# ExtraCore_RST.net
KiCad netlist of a schematic drawn in EAGLE
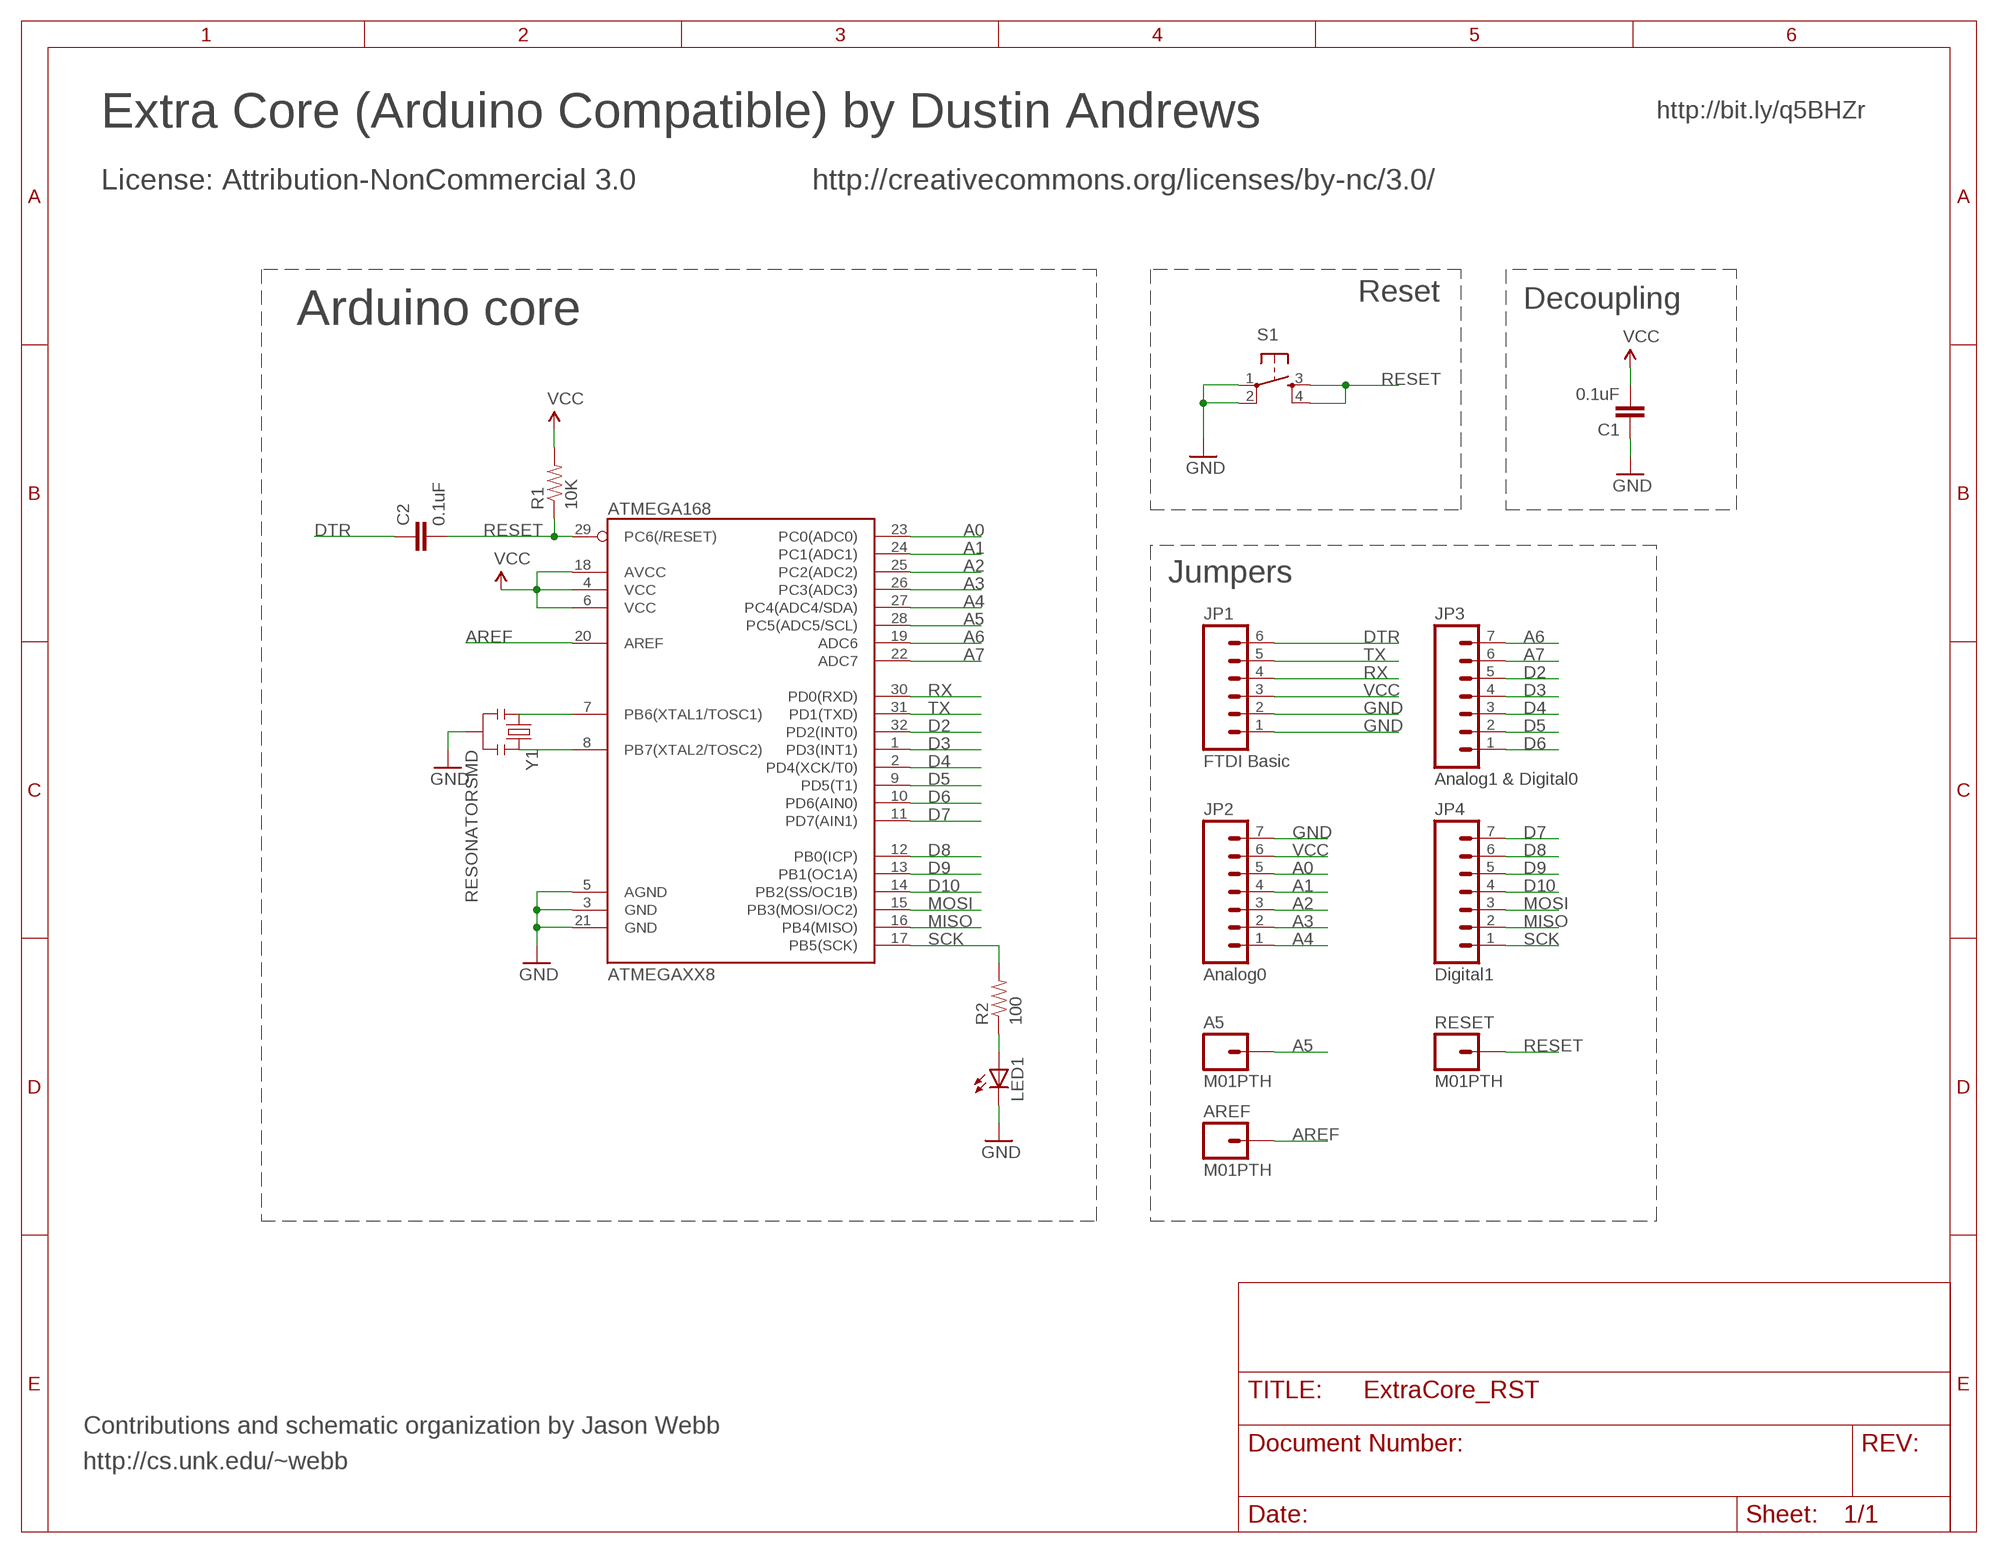
[diagram p0: schematic, sheet 1]

(export (version "E")
  (design (tool "Eeschema 10.0.6"))
  (components
    (comp (ref "A5")
      (value "M01PTH")
      (footprint "eagle-import:1X01")
      (libsource (lib "eagle-import") (part "M01PTH"))
    )
    (comp (ref "AREF")
      (value "M01PTH")
      (footprint "eagle-import:1X01")
      (libsource (lib "eagle-import") (part "M01PTH"))
    )
    (comp (ref "ATMEGAXX8")
      (value "ATMEGA168")
      (footprint "eagle-import:TQFP32-08")
      (libsource (lib "eagle-import") (part "ATMEGA168"))
    )
    (comp (ref "C1")
      (value "0.1uF")
      (footprint "eagle-import:0805")
      (libsource (lib "eagle-import") (part "CAP0805"))
    )
    (comp (ref "C2")
      (value "0.1uF")
      (footprint "eagle-import:0805")
      (libsource (lib "eagle-import") (part "CAP0805"))
    )
    (comp (ref "JP1")
      (value "FTDI Basic")
      (footprint "eagle-import:1X06")
      (libsource (lib "eagle-import") (part "M06SIP"))
    )
    (comp (ref "JP2")
      (value "Analog0")
      (footprint "eagle-import:1X07")
      (libsource (lib "eagle-import") (part "M07"))
    )
    (comp (ref "JP3")
      (value "Analog1 & Digital0")
      (footprint "eagle-import:1X07")
      (libsource (lib "eagle-import") (part "M07"))
    )
    (comp (ref "JP4")
      (value "Digital1")
      (footprint "eagle-import:1X07")
      (libsource (lib "eagle-import") (part "M07"))
    )
    (comp (ref "LED1")
      (value "LEDCHIP-LED0805")
      (footprint "eagle-import:CHIP-LED0805")
      (libsource (lib "eagle-import") (part "LEDCHIP-LED0805"))
    )
    (comp (ref "R1")
      (value "10K")
      (footprint "eagle-import:0805")
      (libsource (lib "eagle-import") (part "RESISTOR0805-RES"))
    )
    (comp (ref "R2")
      (value "100")
      (footprint "eagle-import:0805")
      (libsource (lib "eagle-import") (part "RESISTOR0805-RES"))
    )
    (comp (ref "RESET")
      (value "M01PTH")
      (footprint "eagle-import:1X01")
      (libsource (lib "eagle-import") (part "M01PTH"))
    )
    (comp (ref "S1")
      (value "TAC_SWITCHSMD")
      (footprint "eagle-import:TACTILE_SWITCH_SMD")
      (libsource (lib "eagle-import") (part "TAC_SWITCHSMD"))
    )
    (comp (ref "Y1")
      (value "RESONATORSMD")
      (footprint "eagle-import:RESONATOR-SMD")
      (libsource (lib "eagle-import") (part "RESONATORSMD"))
    )
  )
  (nets
    (net (code "1") (name "/A0") (class "Default")
      (node (ref "ATMEGAXX8") (pin "23") (pinfunction "PC0(ADC0)_23") (pintype "bidirectional"))
      (node (ref "JP2") (pin "5") (pinfunction "5_5") (pintype "passive"))
    )
    (net (code "2") (name "/A1") (class "Default")
      (node (ref "ATMEGAXX8") (pin "24") (pinfunction "PC1(ADC1)_24") (pintype "bidirectional"))
      (node (ref "JP2") (pin "4") (pinfunction "4_4") (pintype "passive"))
    )
    (net (code "3") (name "/A2") (class "Default")
      (node (ref "ATMEGAXX8") (pin "25") (pinfunction "PC2(ADC2)_25") (pintype "bidirectional"))
      (node (ref "JP2") (pin "3") (pinfunction "3_3") (pintype "passive"))
    )
    (net (code "4") (name "/A3") (class "Default")
      (node (ref "ATMEGAXX8") (pin "26") (pinfunction "PC3(ADC3)_26") (pintype "bidirectional"))
      (node (ref "JP2") (pin "2") (pinfunction "2_2") (pintype "passive"))
    )
    (net (code "5") (name "/A4") (class "Default")
      (node (ref "ATMEGAXX8") (pin "27") (pinfunction "PC4(ADC4/SDA)_27") (pintype "bidirectional"))
      (node (ref "JP2") (pin "1") (pinfunction "1_1") (pintype "passive"))
    )
    (net (code "6") (name "/A5") (class "Default")
      (node (ref "A5") (pin "1") (pinfunction "1_1") (pintype "passive"))
      (node (ref "ATMEGAXX8") (pin "28") (pinfunction "PC5(ADC5/SCL)_28") (pintype "bidirectional"))
    )
    (net (code "7") (name "/A6") (class "Default")
      (node (ref "ATMEGAXX8") (pin "19") (pinfunction "ADC6_19") (pintype "bidirectional"))
      (node (ref "JP3") (pin "7") (pinfunction "7_7") (pintype "passive"))
    )
    (net (code "8") (name "/A7") (class "Default")
      (node (ref "ATMEGAXX8") (pin "22") (pinfunction "ADC7_22") (pintype "bidirectional"))
      (node (ref "JP3") (pin "6") (pinfunction "6_6") (pintype "passive"))
    )
    (net (code "9") (name "/AREF") (class "Default")
      (node (ref "AREF") (pin "1") (pinfunction "1_1") (pintype "passive"))
      (node (ref "ATMEGAXX8") (pin "20") (pinfunction "AREF_20") (pintype "bidirectional"))
    )
    (net (code "10") (name "/D2") (class "Default")
      (node (ref "ATMEGAXX8") (pin "32") (pinfunction "PD2(INT0)_32") (pintype "bidirectional"))
      (node (ref "JP3") (pin "5") (pinfunction "5_5") (pintype "passive"))
    )
    (net (code "11") (name "/D3") (class "Default")
      (node (ref "ATMEGAXX8") (pin "1") (pinfunction "PD3(INT1)_1") (pintype "bidirectional"))
      (node (ref "JP3") (pin "4") (pinfunction "4_4") (pintype "passive"))
    )
    (net (code "12") (name "/D4") (class "Default")
      (node (ref "ATMEGAXX8") (pin "2") (pinfunction "PD4(XCK/T0)_2") (pintype "bidirectional"))
      (node (ref "JP3") (pin "3") (pinfunction "3_3") (pintype "passive"))
    )
    (net (code "13") (name "/D5") (class "Default")
      (node (ref "ATMEGAXX8") (pin "9") (pinfunction "PD5(T1)_9") (pintype "bidirectional"))
      (node (ref "JP3") (pin "2") (pinfunction "2_2") (pintype "passive"))
    )
    (net (code "14") (name "/D6") (class "Default")
      (node (ref "ATMEGAXX8") (pin "10") (pinfunction "PD6(AIN0)_10") (pintype "bidirectional"))
      (node (ref "JP3") (pin "1") (pinfunction "1_1") (pintype "passive"))
    )
    (net (code "15") (name "/D7") (class "Default")
      (node (ref "ATMEGAXX8") (pin "11") (pinfunction "PD7(AIN1)_11") (pintype "bidirectional"))
      (node (ref "JP4") (pin "7") (pinfunction "7_7") (pintype "passive"))
    )
    (net (code "16") (name "/D8") (class "Default")
      (node (ref "ATMEGAXX8") (pin "12") (pinfunction "PB0(ICP)_12") (pintype "bidirectional"))
      (node (ref "JP4") (pin "6") (pinfunction "6_6") (pintype "passive"))
    )
    (net (code "17") (name "/D9") (class "Default")
      (node (ref "ATMEGAXX8") (pin "13") (pinfunction "PB1(OC1A)_13") (pintype "bidirectional"))
      (node (ref "JP4") (pin "5") (pinfunction "5_5") (pintype "passive"))
    )
    (net (code "18") (name "/D10") (class "Default")
      (node (ref "ATMEGAXX8") (pin "14") (pinfunction "PB2(SS/OC1B)_14") (pintype "bidirectional"))
      (node (ref "JP4") (pin "4") (pinfunction "4_4") (pintype "passive"))
    )
    (net (code "19") (name "/DTR") (class "Default")
      (node (ref "C2") (pin "1") (pinfunction "1_1") (pintype "passive"))
      (node (ref "JP1") (pin "6") (pinfunction "6_6") (pintype "passive"))
    )
    (net (code "20") (name "/MISO") (class "Default")
      (node (ref "ATMEGAXX8") (pin "16") (pinfunction "PB4(MISO)_16") (pintype "bidirectional"))
      (node (ref "JP4") (pin "2") (pinfunction "2_2") (pintype "passive"))
    )
    (net (code "21") (name "/MOSI") (class "Default")
      (node (ref "ATMEGAXX8") (pin "15") (pinfunction "PB3(MOSI/OC2)_15") (pintype "bidirectional"))
      (node (ref "JP4") (pin "3") (pinfunction "3_3") (pintype "passive"))
    )
    (net (code "22") (name "/RESET") (class "Default")
      (node (ref "ATMEGAXX8") (pin "29") (pinfunction "PC6(/RESET)_29") (pintype "bidirectional"))
      (node (ref "C2") (pin "2") (pinfunction "2_2") (pintype "passive"))
      (node (ref "R1") (pin "1") (pinfunction "1_1") (pintype "passive"))
      (node (ref "RESET") (pin "1") (pinfunction "1_1") (pintype "passive"))
      (node (ref "S1") (pin "3") (pinfunction "3_3") (pintype "passive"))
      (node (ref "S1") (pin "4") (pinfunction "4_4") (pintype "passive"))
    )
    (net (code "23") (name "/RX") (class "Default")
      (node (ref "ATMEGAXX8") (pin "30") (pinfunction "PD0(RXD)_30") (pintype "bidirectional"))
      (node (ref "JP1") (pin "4") (pinfunction "4_4") (pintype "passive"))
    )
    (net (code "24") (name "/SCK") (class "Default")
      (node (ref "ATMEGAXX8") (pin "17") (pinfunction "PB5(SCK)_17") (pintype "bidirectional"))
      (node (ref "JP4") (pin "1") (pinfunction "1_1") (pintype "passive"))
      (node (ref "R2") (pin "2") (pinfunction "2_2") (pintype "passive"))
    )
    (net (code "25") (name "/TX") (class "Default")
      (node (ref "ATMEGAXX8") (pin "31") (pinfunction "PD1(TXD)_31") (pintype "bidirectional"))
      (node (ref "JP1") (pin "5") (pinfunction "5_5") (pintype "passive"))
    )
    (net (code "26") (name "GND") (class "Default")
      (node (ref "ATMEGAXX8") (pin "21") (pinfunction "GND_21") (pintype "bidirectional"))
      (node (ref "ATMEGAXX8") (pin "3") (pinfunction "GND_3") (pintype "bidirectional"))
      (node (ref "ATMEGAXX8") (pin "5") (pinfunction "AGND_5") (pintype "bidirectional"))
      (node (ref "C1") (pin "1") (pinfunction "1_1") (pintype "passive"))
      (node (ref "JP1") (pin "1") (pinfunction "1_1") (pintype "passive"))
      (node (ref "JP1") (pin "2") (pinfunction "2_2") (pintype "passive"))
      (node (ref "JP2") (pin "7") (pinfunction "7_7") (pintype "passive"))
      (node (ref "LED1") (pin "C") (pinfunction "C_C") (pintype "passive"))
      (node (ref "S1") (pin "1") (pinfunction "1_1") (pintype "passive"))
      (node (ref "S1") (pin "2") (pinfunction "2_2") (pintype "passive"))
      (node (ref "Y1") (pin "2") (pinfunction "2_2") (pintype "passive"))
    )
    (net (code "27") (name "Net-(ATMEGAXX8-PB6(XTAL1{slash}TOSC1))") (class "Default")
      (node (ref "ATMEGAXX8") (pin "7") (pinfunction "PB6(XTAL1/TOSC1)_7") (pintype "bidirectional"))
      (node (ref "Y1") (pin "1") (pinfunction "1_1") (pintype "passive"))
    )
    (net (code "28") (name "Net-(ATMEGAXX8-PB7(XTAL2{slash}TOSC2))") (class "Default")
      (node (ref "ATMEGAXX8") (pin "8") (pinfunction "PB7(XTAL2/TOSC2)_8") (pintype "bidirectional"))
      (node (ref "Y1") (pin "3") (pinfunction "3_3") (pintype "passive"))
    )
    (net (code "29") (name "Net-(LED1-PadA)") (class "Default")
      (node (ref "LED1") (pin "A") (pinfunction "A_A") (pintype "passive"))
      (node (ref "R2") (pin "1") (pinfunction "1_1") (pintype "passive"))
    )
    (net (code "30") (name "VCC") (class "Default")
      (node (ref "ATMEGAXX8") (pin "18") (pinfunction "AVCC_18") (pintype "bidirectional"))
      (node (ref "ATMEGAXX8") (pin "4") (pinfunction "VCC_4") (pintype "bidirectional"))
      (node (ref "ATMEGAXX8") (pin "6") (pinfunction "VCC_6") (pintype "bidirectional"))
      (node (ref "C1") (pin "2") (pinfunction "2_2") (pintype "passive"))
      (node (ref "JP1") (pin "3") (pinfunction "3_3") (pintype "passive"))
      (node (ref "JP2") (pin "6") (pinfunction "6_6") (pintype "passive"))
      (node (ref "R1") (pin "2") (pinfunction "2_2") (pintype "passive"))
    )
  )
)
